# ESP32-HWE-Dev-I2C.net
KiCad netlist of a schematic drawn in Altium Designer
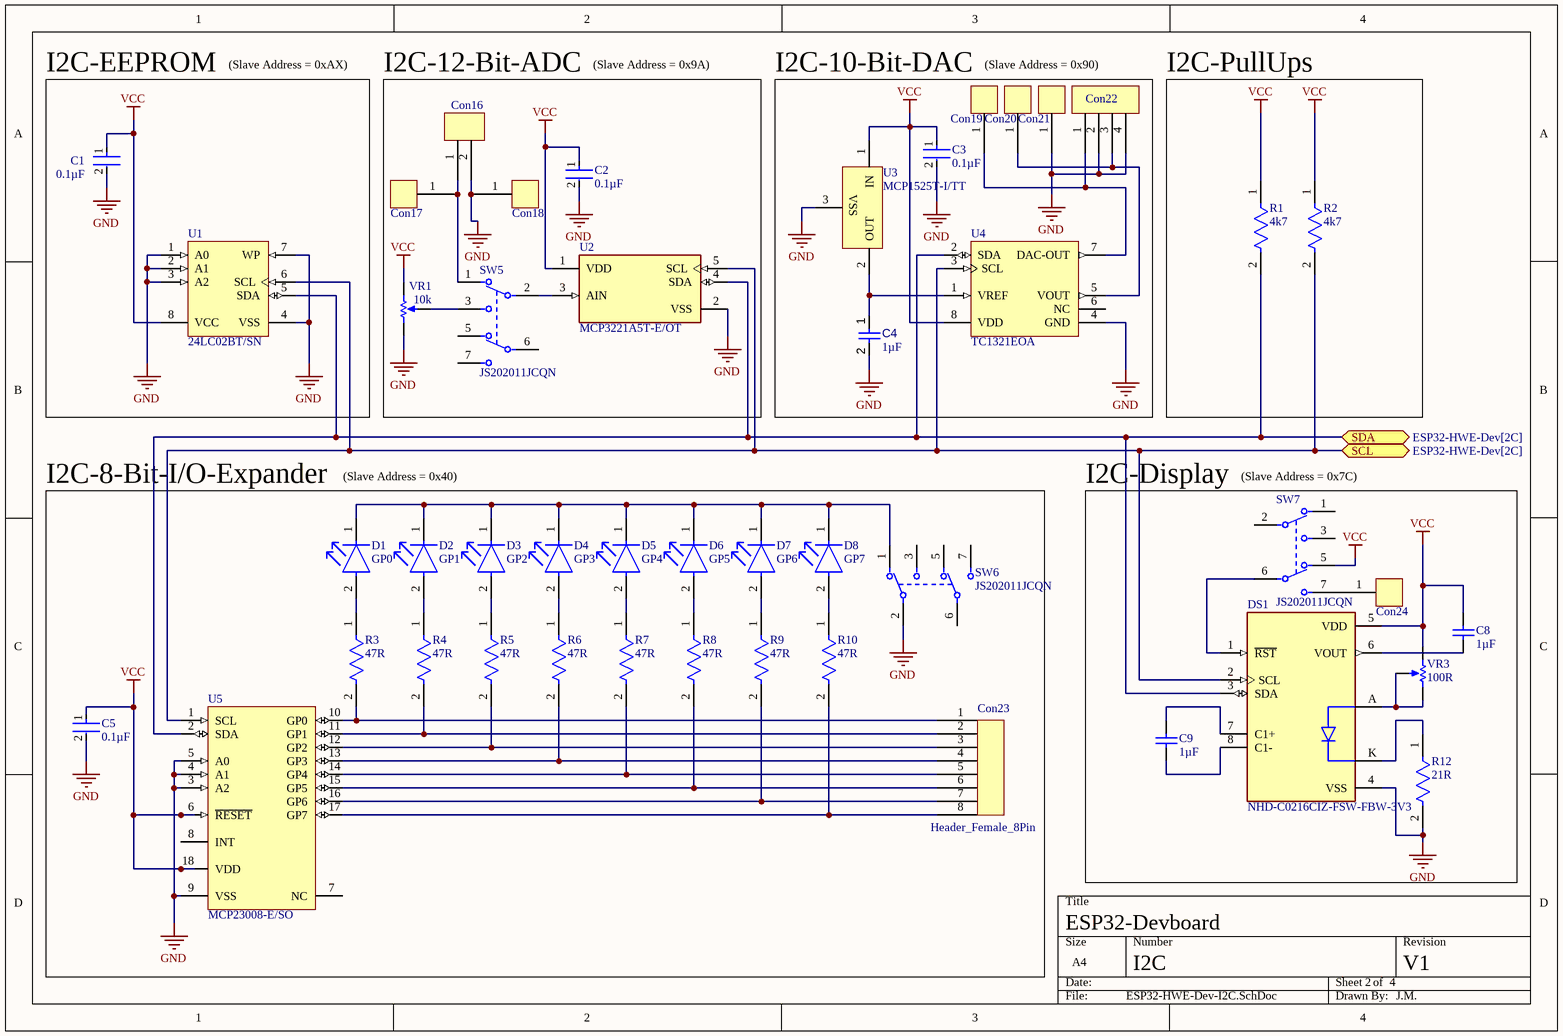
[diagram p0: ESP32-HWE-Dev-I2C.SchDoc]

(export (version "E")
  (design (tool "Eeschema 10.0.6"))
  (components
    (comp (ref "C1")
      (value "0.1µF")
      (footprint "FP-0805-L_2_01_0_2-W_1_25-IPC_C")
      (description "General Purpose Ceramic Capacitor, 0805, 100nF, 10%, X7R, 0.15, 50V")
      (fields (field (name "TOLERANCE") "10%") (field (name "VOLTAGE") "50V"))
      (libsource (lib "Altium Content Vault") (part "02cd4be3c70576c341d710602a673aa"))
    )
    (comp (ref "C2")
      (value "0.1µF")
      (footprint "FP-0805-L_2_01_0_2-W_1_25-IPC_C")
      (description "General Purpose Ceramic Capacitor, 0805, 100nF, 10%, X7R, 0.15, 50V")
      (fields (field (name "TOLERANCE") "10%") (field (name "VOLTAGE") "50V"))
      (libsource (lib "Altium Content Vault") (part "02cd4be3c70576c341d710602a673aa"))
    )
    (comp (ref "C3")
      (value "0.1µF")
      (footprint "FP-0805-L_2_01_0_2-W_1_25-IPC_C")
      (description "General Purpose Ceramic Capacitor, 0805, 100nF, 10%, X7R, 0.15, 50V")
      (fields (field (name "TOLERANCE") "10%") (field (name "VOLTAGE") "50V"))
      (libsource (lib "Altium Content Vault") (part "02cd4be3c70576c341d710602a673aa"))
    )
    (comp (ref "C4")
      (value "1µF")
      (footprint "CAPC2013X135X45NL10T25")
      (description "Chip Capacitor, 1 uF, +/- 10%, 50 V, 0805 (2012 Metric)")
      (fields (field (name "TOLERANCE") "10%") (field (name "Comment") "Capacitor 1 uF +/- 10% 50 V 0805"))
      (libsource (lib "Jakob Metzler") (part "CAP-NP-2"))
    )
    (comp (ref "C5")
      (value "0.1µF")
      (footprint "FP-0805-L_2_01_0_2-W_1_25-IPC_C")
      (description "General Purpose Ceramic Capacitor, 0805, 100nF, 10%, X7R, 0.15, 50V")
      (fields (field (name "TOLERANCE") "10%") (field (name "VOLTAGE") "50V"))
      (libsource (lib "Altium Content Vault") (part "02cd4be3c70576c341d710602a673aa"))
    )
    (comp (ref "C8")
      (value "1µF")
      (footprint "CAPC2013X145X50LL20T25")
      (fields (field (name "MANUFACTURER") "Kemet") (field (name "PART NUMBER") "C0805C105K4PACTU"))
      (libsource (lib "Altium Content Vault") (part "CAP"))
    )
    (comp (ref "C9")
      (value "1µF")
      (footprint "CAPC2013X145X50LL20T25")
      (fields (field (name "MANUFACTURER") "Kemet") (field (name "PART NUMBER") "C0805C105K4PACTU"))
      (libsource (lib "Altium Content Vault") (part "CAP"))
    )
    (comp (ref "Con16")
      (value "Female 2 Pin")
      (footprint "Header_Female_2Pin")
      (libsource (lib "ESP32-HWE-Dev") (part "Header_Female_2Pin"))
    )
    (comp (ref "Con17")
      (value "Solder Nail RTM 1.3")
      (footprint "Solder_Nail_RTM_1.3")
      (libsource (lib "") (part "Solder_Nail_RTM_1.3_2"))
    )
    (comp (ref "Con18")
      (value "Solder Nail RTM 1.3")
      (footprint "Solder_Nail_RTM_1.3")
      (libsource (lib "") (part "Solder_Nail_RTM_1.3_1"))
    )
    (comp (ref "Con19")
      (value "I2C-DAC-DAC-Out")
      (footprint "Solder_Nail_RTM_1.3")
      (libsource (lib "ESP32-HWE-Dev") (part "Solder_Nail_RTM_1.3"))
    )
    (comp (ref "Con20")
      (value "I2C-DAC-Vout")
      (footprint "Solder_Nail_RTM_1.3")
      (libsource (lib "ESP32-HWE-Dev") (part "Solder_Nail_RTM_1.3"))
    )
    (comp (ref "Con21")
      (value "DAC-GND")
      (footprint "Solder_Nail_RTM_1.3")
      (libsource (lib "ESP32-HWE-Dev") (part "Solder_Nail_RTM_1.3"))
    )
    (comp (ref "Con22")
      (value "Female 4 Pin")
      (footprint "Header_Female_4Pin")
      (libsource (lib "ESP32-HWE-Dev") (part "Header_Female_4Pin"))
    )
    (comp (ref "Con23")
      (value "Header_Female_8Pin")
      (footprint "Header_Female_8Pin")
      (libsource (lib "ESP32-HWE-Dev") (part "Header_Female_8Pin"))
    )
    (comp (ref "Con24")
      (value "Solder Nail RTM 1.3")
      (footprint "Solder_Nail_RTM_1.3")
      (libsource (lib "") (part "Solder_Nail_RTM_1.3_1"))
    )
    (comp (ref "D1")
      (value "GP0")
      (footprint "FP-SML-LXT0805IW-TR-MFG")
      (description "LED RED DIFFUSED SMD")
      (libsource (lib "Altium Content Vault") (part "8706943c75ba83719d021d2fdc84c58"))
    )
    (comp (ref "D2")
      (value "GP1")
      (footprint "FP-SML-LXT0805IW-TR-MFG")
      (description "LED RED DIFFUSED SMD")
      (libsource (lib "Altium Content Vault") (part "8706943c75ba83719d021d2fdc84c58"))
    )
    (comp (ref "D3")
      (value "GP2")
      (footprint "FP-SML-LXT0805IW-TR-MFG")
      (description "LED RED DIFFUSED SMD")
      (libsource (lib "Altium Content Vault") (part "8706943c75ba83719d021d2fdc84c58"))
    )
    (comp (ref "D4")
      (value "GP3")
      (footprint "FP-SML-LXT0805IW-TR-MFG")
      (description "LED RED DIFFUSED SMD")
      (libsource (lib "Altium Content Vault") (part "8706943c75ba83719d021d2fdc84c58"))
    )
    (comp (ref "D5")
      (value "GP4")
      (footprint "FP-SML-LXT0805IW-TR-MFG")
      (description "LED RED DIFFUSED SMD")
      (libsource (lib "Altium Content Vault") (part "8706943c75ba83719d021d2fdc84c58"))
    )
    (comp (ref "D6")
      (value "GP5")
      (footprint "FP-SML-LXT0805IW-TR-MFG")
      (description "LED RED DIFFUSED SMD")
      (libsource (lib "Altium Content Vault") (part "8706943c75ba83719d021d2fdc84c58"))
    )
    (comp (ref "D7")
      (value "GP6")
      (footprint "FP-SML-LXT0805IW-TR-MFG")
      (description "LED RED DIFFUSED SMD")
      (libsource (lib "Altium Content Vault") (part "8706943c75ba83719d021d2fdc84c58"))
    )
    (comp (ref "D8")
      (value "GP7")
      (footprint "FP-SML-LXT0805IW-TR-MFG")
      (description "LED RED DIFFUSED SMD")
      (libsource (lib "Altium Content Vault") (part "8706943c75ba83719d021d2fdc84c58"))
    )
    (comp (ref "DS1")
      (value "NHD-C0216CIZ-FSW-FBW-3V3")
      (footprint "NHD-C0216CIZ-FSW-FBW-3V3:LCD_NHD-C0216CIZ-FSW-FBW-3V3")
      (description "Character Display FSTN Transflective 16Char x 2Line 8-Pin")
      (fields (field (name "MF") "{'manufacturer': u'Newhaven'}"))
      (libsource (lib "*") (part "NHD-C0216CIZ-FSW-FBW-3V3"))
    )
    (comp (ref "R1")
      (value "4k7")
      (footprint "FP-AC0805-MFG")
      (description "RES SMD 4.7K OHM 5% 1/8W 0805")
      (fields (field (name "MANUFACTURER") "Yageo") (field (name "TOLERANCE") "0.05"))
      (libsource (lib "Altium Content Vault") (part "1029c3af85768c4190bb7ad29bc67b5"))
    )
    (comp (ref "R2")
      (value "4k7")
      (footprint "FP-AC0805-MFG")
      (description "RES SMD 4.7K OHM 5% 1/8W 0805")
      (fields (field (name "MANUFACTURER") "Yageo") (field (name "TOLERANCE") "0.05"))
      (libsource (lib "Altium Content Vault") (part "1029c3af85768c4190bb7ad29bc67b5"))
    )
    (comp (ref "R3")
      (value "47R")
      (footprint "FP-AC0805-MFG")
      (description "RES SMD 4.7K OHM 5% 1/8W 0805")
      (fields (field (name "MANUFACTURER") "Yageo") (field (name "TOLERANCE") "0.05"))
      (libsource (lib "Altium Content Vault") (part "1029c3af85768c4190bb7ad29bc67b5"))
    )
    (comp (ref "R4")
      (value "47R")
      (footprint "FP-AC0805-MFG")
      (description "RES SMD 4.7K OHM 5% 1/8W 0805")
      (fields (field (name "MANUFACTURER") "Yageo") (field (name "TOLERANCE") "0.05"))
      (libsource (lib "Altium Content Vault") (part "1029c3af85768c4190bb7ad29bc67b5"))
    )
    (comp (ref "R5")
      (value "47R")
      (footprint "FP-AC0805-MFG")
      (description "RES SMD 4.7K OHM 5% 1/8W 0805")
      (fields (field (name "MANUFACTURER") "Yageo") (field (name "TOLERANCE") "0.05"))
      (libsource (lib "Altium Content Vault") (part "1029c3af85768c4190bb7ad29bc67b5"))
    )
    (comp (ref "R6")
      (value "47R")
      (footprint "FP-AC0805-MFG")
      (description "RES SMD 4.7K OHM 5% 1/8W 0805")
      (fields (field (name "MANUFACTURER") "Yageo") (field (name "TOLERANCE") "0.05"))
      (libsource (lib "Altium Content Vault") (part "1029c3af85768c4190bb7ad29bc67b5"))
    )
    (comp (ref "R7")
      (value "47R")
      (footprint "FP-AC0805-MFG")
      (description "RES SMD 4.7K OHM 5% 1/8W 0805")
      (fields (field (name "MANUFACTURER") "Yageo") (field (name "TOLERANCE") "0.05"))
      (libsource (lib "Altium Content Vault") (part "1029c3af85768c4190bb7ad29bc67b5"))
    )
    (comp (ref "R8")
      (value "47R")
      (footprint "FP-AC0805-MFG")
      (description "RES SMD 4.7K OHM 5% 1/8W 0805")
      (fields (field (name "MANUFACTURER") "Yageo") (field (name "TOLERANCE") "0.05"))
      (libsource (lib "Altium Content Vault") (part "1029c3af85768c4190bb7ad29bc67b5"))
    )
    (comp (ref "R9")
      (value "47R")
      (footprint "FP-AC0805-MFG")
      (description "RES SMD 4.7K OHM 5% 1/8W 0805")
      (fields (field (name "MANUFACTURER") "Yageo") (field (name "TOLERANCE") "0.05"))
      (libsource (lib "Altium Content Vault") (part "1029c3af85768c4190bb7ad29bc67b5"))
    )
    (comp (ref "R10")
      (value "47R")
      (footprint "FP-AC0805-MFG")
      (description "RES SMD 4.7K OHM 5% 1/8W 0805")
      (fields (field (name "MANUFACTURER") "Yageo") (field (name "TOLERANCE") "0.05"))
      (libsource (lib "Altium Content Vault") (part "1029c3af85768c4190bb7ad29bc67b5"))
    )
    (comp (ref "R12")
      (value "21R")
      (footprint "FP-AC0805-MFG")
      (description "RES SMD 4.7K OHM 5% 1/8W 0805")
      (fields (field (name "MANUFACTURER") "Yageo") (field (name "TOLERANCE") "0.05"))
      (libsource (lib "Altium Content Vault") (part "1029c3af85768c4190bb7ad29bc67b5"))
    )
    (comp (ref "SW5")
      (value "JS202011JCQN")
      (footprint "FP-JS202011JCQN-MFG")
      (description "SWITCH SLIDE DPDT 300MA 6V")
      (libsource (lib "Altium Content Vault") (part "6b3bc4f94d389b2e45f6181d1f21823"))
    )
    (comp (ref "SW6")
      (value "JS202011JCQN")
      (footprint "FP-JS202011JCQN-MFG")
      (description "SWITCH SLIDE DPDT 300MA 6V")
      (libsource (lib "Altium Content Vault") (part "6b3bc4f94d389b2e45f6181d1f21823"))
    )
    (comp (ref "SW7")
      (value "JS202011JCQN")
      (footprint "FP-JS202011JCQN-MFG")
      (description "SWITCH SLIDE DPDT 300MA 6V")
      (libsource (lib "Altium Content Vault") (part "6b3bc4f94d389b2e45f6181d1f21823"))
    )
    (comp (ref "U1")
      (value "24LC02BT/SN")
      (footprint "SOIC-SN8_N")
      (description "2Kbit, 400kHz, 2.5V, I2C Serial EEPROM, 8-Pin SOIC 150mil, Commercial Temperature, Tape and Reel")
      (libsource (lib "Altium Content Vault") (part "MEM-SEEPROM-34AA02-IL8"))
    )
    (comp (ref "U2")
      (value "MCP3221A5T-E/OT")
      (footprint "FP-C04-091-OT-IPC_A")
      (description "IC ADC 12BIT SAR SOT23-5")
      (libsource (lib "Altium Content Vault") (part "267732dee5d01d5c010a5af9ce19d91"))
    )
    (comp (ref "U3")
      (value "MCP1525T-I/TT")
      (footprint "SOT-23-TT3_M")
      (description "2.5V Voltage Reference, 3-Pin SOT-23, Industrial Temperature, Tape and Reel")
      (libsource (lib "Altium Content Vault") (part "PM-REF-MCP15XX-SOT3"))
    )
    (comp (ref "U4")
      (value "TC1321EOA")
      (footprint "SOIC-OA8_L")
      (libsource (lib "Altium Content Vault") (part "CON-DAC-TC132X-8"))
    )
    (comp (ref "U5")
      (value "MCP23008-E/SO")
      (footprint "SOIC-SO18_N")
      (description "8-Bit I/O Expander with Serial Interface, 18-Pin SOIC, Extended Temperature")
      (libsource (lib "Altium Content Vault") (part "PR-BUSIC-MCP23008-18"))
    )
    (comp (ref "VR1")
      (value "10k")
      (footprint "BOUR-3362P")
      (description "Square Trimpot(R) Trimming Potentiometer, 10 KOhm, 300 V, -55 to 125 degC, 3-Pin THD, RoHS, Tube")
      (fields (field (name "TOLERANCE") "1%"))
      (libsource (lib "Altium Content Vault") (part "RES-POT-3"))
    )
    (comp (ref "VR3")
      (value "100R")
      (footprint "BOUR-3362P")
      (description "Square Trimpot(R) Trimming Potentiometer, 10 KOhm, 300 V, -55 to 125 degC, 3-Pin THD, RoHS, Tube")
      (fields (field (name "TOLERANCE") "1%"))
      (libsource (lib "Altium Content Vault") (part "RES-POT-3"))
    )
  )
  (nets
    (net (code "1") (name "/SCL") (class "Default")
      (node (ref "DS1") (pin "2") (pinfunction "SCL_2") (pintype "input"))
      (node (ref "R2") (pin "2") (pinfunction "2_2") (pintype "passive"))
      (node (ref "U1") (pin "6") (pinfunction "SCL_6") (pintype "input"))
      (node (ref "U2") (pin "5") (pinfunction "SCL_5") (pintype "input"))
      (node (ref "U4") (pin "3") (pinfunction "SCL_3") (pintype "input"))
      (node (ref "U5") (pin "1") (pinfunction "SCL_1") (pintype "input"))
    )
    (net (code "2") (name "/SDA") (class "Default")
      (node (ref "DS1") (pin "3") (pinfunction "SDA_3") (pintype "bidirectional"))
      (node (ref "R1") (pin "2") (pinfunction "2_2") (pintype "passive"))
      (node (ref "U1") (pin "5") (pinfunction "SDA_5") (pintype "bidirectional"))
      (node (ref "U2") (pin "4") (pinfunction "SDA_4") (pintype "bidirectional"))
      (node (ref "U4") (pin "2") (pinfunction "SDA_2") (pintype "bidirectional"))
      (node (ref "U5") (pin "2") (pinfunction "SDA_2") (pintype "bidirectional"))
    )
    (net (code "3") (name "GND") (class "Default")
      (node (ref "C1") (pin "2") (pinfunction "2_2") (pintype "passive"))
      (node (ref "C2") (pin "2") (pinfunction "2_2") (pintype "passive"))
      (node (ref "C3") (pin "2") (pinfunction "2_2") (pintype "passive"))
      (node (ref "C4") (pin "2") (pinfunction "2_2") (pintype "passive"))
      (node (ref "C5") (pin "2") (pinfunction "2_2") (pintype "passive"))
      (node (ref "Con16") (pin "2") (pintype "passive"))
      (node (ref "Con18") (pin "1") (pintype "passive"))
      (node (ref "Con21") (pin "1") (pintype "passive"))
      (node (ref "Con22") (pin "2") (pintype "passive"))
      (node (ref "Con22") (pin "4") (pintype "passive"))
      (node (ref "DS1") (pin "4") (pinfunction "VSS_4") (pintype "power_in"))
      (node (ref "R12") (pin "2") (pinfunction "2_2") (pintype "passive"))
      (node (ref "SW6") (pin "2") (pinfunction "1_C_2") (pintype "passive"))
      (node (ref "U1") (pin "1") (pinfunction "A0_1") (pintype "input"))
      (node (ref "U1") (pin "2") (pinfunction "A1_2") (pintype "input"))
      (node (ref "U1") (pin "3") (pinfunction "A2_3") (pintype "input"))
      (node (ref "U1") (pin "4") (pinfunction "VSS_4") (pintype "power_in"))
      (node (ref "U1") (pin "7") (pinfunction "WP_7") (pintype "input"))
      (node (ref "U2") (pin "2") (pinfunction "VSS_2") (pintype "power_in"))
      (node (ref "U3") (pin "3") (pinfunction "VSS_3") (pintype "power_in"))
      (node (ref "U4") (pin "4") (pinfunction "GND_4") (pintype "power_in"))
      (node (ref "U5") (pin "3") (pinfunction "A2_3") (pintype "input"))
      (node (ref "U5") (pin "4") (pinfunction "A1_4") (pintype "input"))
      (node (ref "U5") (pin "5") (pinfunction "A0_5") (pintype "input"))
      (node (ref "U5") (pin "9") (pinfunction "VSS_9") (pintype "power_in"))
      (node (ref "VR1") (pin "1") (pinfunction "CCW_1") (pintype "passive"))
    )
    (net (code "4") (name "Net-(Con16-Pad1)") (class "Default")
      (node (ref "Con16") (pin "1") (pintype "passive"))
      (node (ref "Con17") (pin "1") (pintype "passive"))
      (node (ref "SW5") (pin "1") (pinfunction "1_1") (pintype "passive"))
    )
    (net (code "5") (name "Net-(Con24-Pad1)") (class "Default")
      (node (ref "Con24") (pin "1") (pintype "passive"))
      (node (ref "SW7") (pin "7") (pinfunction "7_7") (pintype "passive"))
    )
    (net (code "6") (name "Net-(D1-A)") (class "Default")
      (node (ref "D1") (pin "2") (pinfunction "A_2") (pintype "passive"))
      (node (ref "R3") (pin "1") (pinfunction "1_1") (pintype "passive"))
    )
    (net (code "7") (name "Net-(D1-C)") (class "Default")
      (node (ref "D1") (pin "1") (pinfunction "C_1") (pintype "passive"))
      (node (ref "D2") (pin "1") (pinfunction "C_1") (pintype "passive"))
      (node (ref "D3") (pin "1") (pinfunction "C_1") (pintype "passive"))
      (node (ref "D4") (pin "1") (pinfunction "C_1") (pintype "passive"))
      (node (ref "D5") (pin "1") (pinfunction "C_1") (pintype "passive"))
      (node (ref "D6") (pin "1") (pinfunction "C_1") (pintype "passive"))
      (node (ref "D7") (pin "1") (pinfunction "C_1") (pintype "passive"))
      (node (ref "D8") (pin "1") (pinfunction "C_1") (pintype "passive"))
      (node (ref "SW6") (pin "1") (pinfunction "1_1") (pintype "passive"))
    )
    (net (code "8") (name "Net-(D2-A)") (class "Default")
      (node (ref "D2") (pin "2") (pinfunction "A_2") (pintype "passive"))
      (node (ref "R4") (pin "1") (pinfunction "1_1") (pintype "passive"))
    )
    (net (code "9") (name "Net-(D3-A)") (class "Default")
      (node (ref "D3") (pin "2") (pinfunction "A_2") (pintype "passive"))
      (node (ref "R5") (pin "1") (pinfunction "1_1") (pintype "passive"))
    )
    (net (code "10") (name "Net-(D4-A)") (class "Default")
      (node (ref "D4") (pin "2") (pinfunction "A_2") (pintype "passive"))
      (node (ref "R6") (pin "1") (pinfunction "1_1") (pintype "passive"))
    )
    (net (code "11") (name "Net-(D5-A)") (class "Default")
      (node (ref "D5") (pin "2") (pinfunction "A_2") (pintype "passive"))
      (node (ref "R7") (pin "1") (pinfunction "1_1") (pintype "passive"))
    )
    (net (code "12") (name "Net-(D6-A)") (class "Default")
      (node (ref "D6") (pin "2") (pinfunction "A_2") (pintype "passive"))
      (node (ref "R8") (pin "1") (pinfunction "1_1") (pintype "passive"))
    )
    (net (code "13") (name "Net-(D7-A)") (class "Default")
      (node (ref "D7") (pin "2") (pinfunction "A_2") (pintype "passive"))
      (node (ref "R9") (pin "1") (pinfunction "1_1") (pintype "passive"))
    )
    (net (code "14") (name "Net-(D8-A)") (class "Default")
      (node (ref "D8") (pin "2") (pinfunction "A_2") (pintype "passive"))
      (node (ref "R10") (pin "1") (pinfunction "1_1") (pintype "passive"))
    )
    (net (code "15") (name "Net-(DS1-C1+)") (class "Default")
      (node (ref "C9") (pin "2") (pinfunction "2_2") (pintype "passive"))
      (node (ref "DS1") (pin "7") (pinfunction "C1+_7") (pintype "passive"))
    )
    (net (code "16") (name "Net-(DS1-C1-)") (class "Default")
      (node (ref "C9") (pin "1") (pinfunction "1_1") (pintype "passive"))
      (node (ref "DS1") (pin "8") (pinfunction "C1-_8") (pintype "passive"))
    )
    (net (code "17") (name "Net-(DS1-PadK)") (class "Default")
      (node (ref "DS1") (pin "K") (pinfunction "K_K") (pintype "passive"))
      (node (ref "R12") (pin "1") (pinfunction "1_1") (pintype "passive"))
    )
    (net (code "18") (name "Net-(DS1-VOUT)") (class "Default")
      (node (ref "C8") (pin "1") (pinfunction "1_1") (pintype "passive"))
      (node (ref "DS1") (pin "6") (pinfunction "VOUT_6") (pintype "output"))
    )
    (net (code "19") (name "Net-(DS1-~{RST})") (class "Default")
      (node (ref "DS1") (pin "1") (pinfunction "~{RST}_1") (pintype "input"))
      (node (ref "SW7") (pin "6") (pinfunction "2_C_6") (pintype "passive"))
    )
    (net (code "20") (name "Net-(SW5-1_C)") (class "Default")
      (node (ref "SW5") (pin "2") (pinfunction "1_C_2") (pintype "passive"))
      (node (ref "U2") (pin "3") (pinfunction "AIN_3") (pintype "input"))
    )
    (net (code "21") (name "Net-(U3-OUT)") (class "Default")
      (node (ref "C4") (pin "1") (pinfunction "1_1") (pintype "passive"))
      (node (ref "U3") (pin "2") (pinfunction "OUT_2") (pintype "power_in"))
      (node (ref "U4") (pin "1") (pinfunction "VREF_1") (pintype "input"))
    )
    (net (code "22") (name "Net-(U4-DAC-OUT)") (class "Default")
      (node (ref "Con19") (pin "1") (pintype "passive"))
      (node (ref "Con22") (pin "1") (pintype "passive"))
      (node (ref "U4") (pin "7") (pinfunction "DAC-OUT_7") (pintype "output"))
    )
    (net (code "23") (name "Net-(U4-VOUT)") (class "Default")
      (node (ref "Con20") (pin "1") (pintype "passive"))
      (node (ref "Con22") (pin "3") (pintype "passive"))
      (node (ref "U4") (pin "5") (pinfunction "VOUT_5") (pintype "output"))
    )
    (net (code "24") (name "Net-(U5-GP0)") (class "Default")
      (node (ref "Con23") (pin "1") (pinfunction "1_1") (pintype "passive"))
      (node (ref "R3") (pin "2") (pinfunction "2_2") (pintype "passive"))
      (node (ref "U5") (pin "10") (pinfunction "GP0_10") (pintype "bidirectional"))
    )
    (net (code "25") (name "Net-(U5-GP1)") (class "Default")
      (node (ref "Con23") (pin "2") (pinfunction "2_2") (pintype "passive"))
      (node (ref "R4") (pin "2") (pinfunction "2_2") (pintype "passive"))
      (node (ref "U5") (pin "11") (pinfunction "GP1_11") (pintype "bidirectional"))
    )
    (net (code "26") (name "Net-(U5-GP2)") (class "Default")
      (node (ref "Con23") (pin "3") (pinfunction "3_3") (pintype "passive"))
      (node (ref "R5") (pin "2") (pinfunction "2_2") (pintype "passive"))
      (node (ref "U5") (pin "12") (pinfunction "GP2_12") (pintype "bidirectional"))
    )
    (net (code "27") (name "Net-(U5-GP3)") (class "Default")
      (node (ref "Con23") (pin "4") (pinfunction "4_4") (pintype "passive"))
      (node (ref "R6") (pin "2") (pinfunction "2_2") (pintype "passive"))
      (node (ref "U5") (pin "13") (pinfunction "GP3_13") (pintype "bidirectional"))
    )
    (net (code "28") (name "Net-(U5-GP4)") (class "Default")
      (node (ref "Con23") (pin "5") (pinfunction "5_5") (pintype "passive"))
      (node (ref "R7") (pin "2") (pinfunction "2_2") (pintype "passive"))
      (node (ref "U5") (pin "14") (pinfunction "GP4_14") (pintype "bidirectional"))
    )
    (net (code "29") (name "Net-(U5-GP5)") (class "Default")
      (node (ref "Con23") (pin "6") (pinfunction "6_6") (pintype "passive"))
      (node (ref "R8") (pin "2") (pinfunction "2_2") (pintype "passive"))
      (node (ref "U5") (pin "15") (pinfunction "GP5_15") (pintype "bidirectional"))
    )
    (net (code "30") (name "Net-(U5-GP6)") (class "Default")
      (node (ref "Con23") (pin "7") (pinfunction "7_7") (pintype "passive"))
      (node (ref "R9") (pin "2") (pinfunction "2_2") (pintype "passive"))
      (node (ref "U5") (pin "16") (pinfunction "GP6_16") (pintype "bidirectional"))
    )
    (net (code "31") (name "Net-(U5-GP7)") (class "Default")
      (node (ref "Con23") (pin "8") (pinfunction "8_8") (pintype "passive"))
      (node (ref "R10") (pin "2") (pinfunction "2_2") (pintype "passive"))
      (node (ref "U5") (pin "17") (pinfunction "GP7_17") (pintype "bidirectional"))
    )
    (net (code "32") (name "Net-(VR1-S)") (class "Default")
      (node (ref "SW5") (pin "3") (pinfunction "3_3") (pintype "passive"))
      (node (ref "VR1") (pin "2") (pinfunction "S_2") (pintype "passive"))
    )
    (net (code "33") (name "Net-(VR3-CW)") (class "Default")
      (node (ref "DS1") (pin "A") (pinfunction "A_A") (pintype "passive"))
      (node (ref "VR3") (pin "2") (pinfunction "S_2") (pintype "passive"))
      (node (ref "VR3") (pin "3") (pinfunction "CW_3") (pintype "passive"))
    )
    (net (code "34") (name "VCC") (class "Default")
      (node (ref "C1") (pin "1") (pinfunction "1_1") (pintype "passive"))
      (node (ref "C2") (pin "1") (pinfunction "1_1") (pintype "passive"))
      (node (ref "C3") (pin "1") (pinfunction "1_1") (pintype "passive"))
      (node (ref "C5") (pin "1") (pinfunction "1_1") (pintype "passive"))
      (node (ref "C8") (pin "2") (pinfunction "2_2") (pintype "passive"))
      (node (ref "DS1") (pin "5") (pinfunction "VDD_5") (pintype "power_in"))
      (node (ref "R1") (pin "1") (pinfunction "1_1") (pintype "passive"))
      (node (ref "R2") (pin "1") (pinfunction "1_1") (pintype "passive"))
      (node (ref "SW7") (pin "5") (pinfunction "5_5") (pintype "passive"))
      (node (ref "U1") (pin "8") (pinfunction "VCC_8") (pintype "power_in"))
      (node (ref "U2") (pin "1") (pinfunction "VDD_1") (pintype "power_in"))
      (node (ref "U3") (pin "1") (pinfunction "IN_1") (pintype "power_in"))
      (node (ref "U4") (pin "8") (pinfunction "VDD_8") (pintype "power_in"))
      (node (ref "U5") (pin "18") (pinfunction "VDD_18") (pintype "power_in"))
      (node (ref "U5") (pin "6") (pinfunction "~{RESET}_6") (pintype "input"))
      (node (ref "VR1") (pin "3") (pinfunction "CW_3") (pintype "passive"))
      (node (ref "VR3") (pin "1") (pinfunction "CCW_1") (pintype "passive"))
    )
    (net (code "35") (name "unconnected-(SW5-2_C-Pad6)") (class "Default")
      (node (ref "SW5") (pin "6") (pinfunction "2_C_6") (pintype "passive"))
    )
    (net (code "36") (name "unconnected-(SW5-Pad5)") (class "Default")
      (node (ref "SW5") (pin "5") (pinfunction "5_5") (pintype "passive"))
    )
    (net (code "37") (name "unconnected-(SW5-Pad7)") (class "Default")
      (node (ref "SW5") (pin "7") (pinfunction "7_7") (pintype "passive"))
    )
    (net (code "38") (name "unconnected-(SW6-2_C-Pad6)") (class "Default")
      (node (ref "SW6") (pin "6") (pinfunction "2_C_6") (pintype "passive"))
    )
    (net (code "39") (name "unconnected-(SW6-Pad3)") (class "Default")
      (node (ref "SW6") (pin "3") (pinfunction "3_3") (pintype "passive"))
    )
    (net (code "40") (name "unconnected-(SW6-Pad5)") (class "Default")
      (node (ref "SW6") (pin "5") (pinfunction "5_5") (pintype "passive"))
    )
    (net (code "41") (name "unconnected-(SW6-Pad7)") (class "Default")
      (node (ref "SW6") (pin "7") (pinfunction "7_7") (pintype "passive"))
    )
    (net (code "42") (name "unconnected-(SW7-1_C-Pad2)") (class "Default")
      (node (ref "SW7") (pin "2") (pinfunction "1_C_2") (pintype "passive"))
    )
    (net (code "43") (name "unconnected-(SW7-Pad1)") (class "Default")
      (node (ref "SW7") (pin "1") (pinfunction "1_1") (pintype "passive"))
    )
    (net (code "44") (name "unconnected-(SW7-Pad3)") (class "Default")
      (node (ref "SW7") (pin "3") (pinfunction "3_3") (pintype "passive"))
    )
    (net (code "45") (name "unconnected-(U4-NC-Pad6)") (class "Default")
      (node (ref "U4") (pin "6") (pinfunction "NC_6") (pintype "passive"))
    )
    (net (code "46") (name "unconnected-(U5-INT-Pad8)") (class "Default")
      (node (ref "U5") (pin "8") (pinfunction "INT_8") (pintype "open_collector"))
    )
    (net (code "47") (name "unconnected-(U5-NC-Pad7)") (class "Default")
      (node (ref "U5") (pin "7") (pinfunction "NC_7") (pintype "passive"))
    )
  )
)
